# Sheet4.net
KiCad netlist of a schematic drawn in Altium Designer
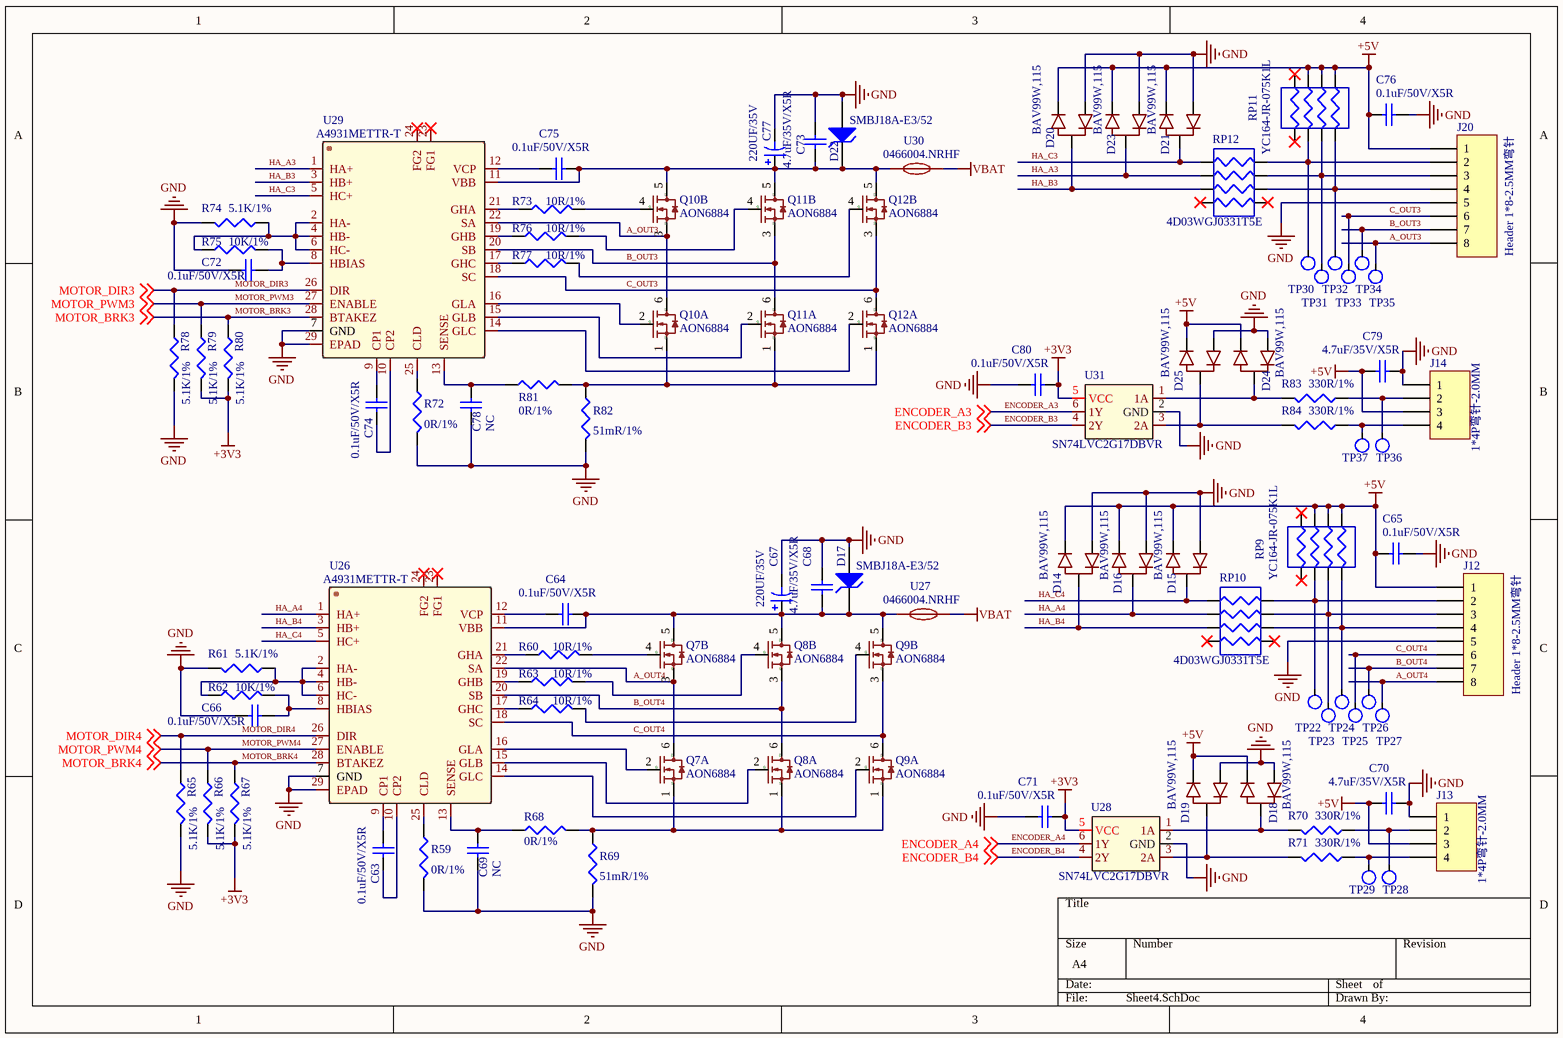
[diagram p0: Sheet4.SchDoc]

(export (version "E")
  (design (tool "Eeschema 10.0.6"))
  (components
    (comp (ref "C63")
      (value "0.1uF/50V/X5R")
      (footprint "C0603")
      (description "Capacitor (Semiconductor SIM Model)")
      (fields (field (name "PUBLISHER") "Altium Limited"))
      (libsource (lib "Miscellaneous Devices") (part "Cap Semi"))
    )
    (comp (ref "C64")
      (value "0.1uF/50V/X5R")
      (footprint "C0603")
      (description "Capacitor (Semiconductor SIM Model)")
      (fields (field (name "PUBLISHER") "Altium Limited"))
      (libsource (lib "Miscellaneous Devices") (part "Cap Semi"))
    )
    (comp (ref "C65")
      (value "0.1uF/50V/X5R")
      (footprint "C0603")
      (description "Capacitor (Semiconductor SIM Model)")
      (fields (field (name "PUBLISHER") "Altium Limited"))
      (libsource (lib "Miscellaneous Devices") (part "Cap Semi"))
    )
    (comp (ref "C66")
      (value "0.1uF/50V/X5R")
      (footprint "C0603")
      (description "Capacitor (Semiconductor SIM Model)")
      (fields (field (name "PUBLISHER") "Altium Limited"))
      (libsource (lib "Miscellaneous Devices") (part "Cap Semi"))
    )
    (comp (ref "C67")
      (value "220UF/35V")
      (footprint "SMD_8X10.2")
      (description "Polarized Capacitor (Radial)")
      (fields (field (name "PUBLISHER") "Altium Limited"))
      (libsource (lib "Miscellaneous Devices") (part "Cap Pol1"))
    )
    (comp (ref "C68")
      (value "4.7uF/35V/X5R")
      (footprint "C0805")
      (description "Capacitor (Semiconductor SIM Model)")
      (fields (field (name "PUBLISHER") "Altium Limited"))
      (libsource (lib "Miscellaneous Devices") (part "Cap Semi"))
    )
    (comp (ref "C69")
      (value "NC")
      (footprint "C0603")
      (description "Capacitor (Semiconductor SIM Model)")
      (fields (field (name "PUBLISHER") "Altium Limited"))
      (libsource (lib "Miscellaneous Devices") (part "Cap Semi"))
    )
    (comp (ref "C70")
      (value "4.7uF/35V/X5R")
      (footprint "C0603")
      (description "Capacitor (Semiconductor SIM Model)")
      (fields (field (name "PUBLISHER") "Altium Limited"))
      (libsource (lib "Miscellaneous Devices") (part "Cap Semi"))
    )
    (comp (ref "C71")
      (value "0.1uF/50V/X5R")
      (footprint "C0603")
      (description "Capacitor (Semiconductor SIM Model)")
      (fields (field (name "PUBLISHER") "Altium Limited"))
      (libsource (lib "Miscellaneous Devices") (part "Cap Semi"))
    )
    (comp (ref "C72")
      (value "0.1uF/50V/X5R")
      (footprint "C0603")
      (description "Capacitor (Semiconductor SIM Model)")
      (fields (field (name "PUBLISHER") "Altium Limited"))
      (libsource (lib "Miscellaneous Devices") (part "Cap Semi"))
    )
    (comp (ref "C73")
      (value "4.7uF/35V/X5R")
      (footprint "C0805")
      (description "Capacitor (Semiconductor SIM Model)")
      (fields (field (name "PUBLISHER") "Altium Limited"))
      (libsource (lib "Miscellaneous Devices") (part "Cap Semi"))
    )
    (comp (ref "C74")
      (value "0.1uF/50V/X5R")
      (footprint "C0603")
      (description "Capacitor (Semiconductor SIM Model)")
      (fields (field (name "PUBLISHER") "Altium Limited"))
      (libsource (lib "Miscellaneous Devices") (part "Cap Semi"))
    )
    (comp (ref "C75")
      (value "0.1uF/50V/X5R")
      (footprint "C0603")
      (description "Capacitor (Semiconductor SIM Model)")
      (fields (field (name "PUBLISHER") "Altium Limited"))
      (libsource (lib "Miscellaneous Devices") (part "Cap Semi"))
    )
    (comp (ref "C76")
      (value "0.1uF/50V/X5R")
      (footprint "C0603")
      (description "Capacitor (Semiconductor SIM Model)")
      (fields (field (name "PUBLISHER") "Altium Limited"))
      (libsource (lib "Miscellaneous Devices") (part "Cap Semi"))
    )
    (comp (ref "C77")
      (value "220UF/35V")
      (footprint "SMD_8X10.2")
      (description "Polarized Capacitor (Radial)")
      (fields (field (name "PUBLISHER") "Altium Limited"))
      (libsource (lib "Miscellaneous Devices") (part "Cap Pol1"))
    )
    (comp (ref "C78")
      (value "NC")
      (footprint "C0603")
      (description "Capacitor (Semiconductor SIM Model)")
      (fields (field (name "PUBLISHER") "Altium Limited"))
      (libsource (lib "Miscellaneous Devices") (part "Cap Semi"))
    )
    (comp (ref "C79")
      (value "4.7uF/35V/X5R")
      (footprint "C0603")
      (description "Capacitor (Semiconductor SIM Model)")
      (fields (field (name "PUBLISHER") "Altium Limited"))
      (libsource (lib "Miscellaneous Devices") (part "Cap Semi"))
    )
    (comp (ref "C80")
      (value "0.1uF/50V/X5R")
      (footprint "C0603")
      (description "Capacitor (Semiconductor SIM Model)")
      (fields (field (name "PUBLISHER") "Altium Limited"))
      (libsource (lib "Miscellaneous Devices") (part "Cap Semi"))
    )
    (comp (ref "D14") (value "BAV99W,115") (libsource (lib "Schlib1") (part "BAV99W,115")))
    (comp (ref "D15") (value "BAV99W,115") (libsource (lib "Schlib1") (part "BAV99W,115")))
    (comp (ref "D16") (value "BAV99W,115") (libsource (lib "Schlib1") (part "BAV99W,115")))
    (comp (ref "D17")
      (value "SMBJ18A-E3/52")
      (footprint "SMB")
      (description "Zener Diode")
      (fields (field (name "PUBLISHER") "Altium Limited"))
      (libsource (lib "Miscellaneous Devices") (part "D Zener"))
    )
    (comp (ref "D18") (value "BAV99W,115") (libsource (lib "Schlib1") (part "BAV99W,115")))
    (comp (ref "D19") (value "BAV99W,115") (libsource (lib "Schlib1") (part "BAV99W,115")))
    (comp (ref "D20") (value "BAV99W,115") (libsource (lib "Schlib1") (part "BAV99W,115")))
    (comp (ref "D21") (value "BAV99W,115") (libsource (lib "Schlib1") (part "BAV99W,115")))
    (comp (ref "D22")
      (value "SMBJ18A-E3/52")
      (footprint "SMB")
      (description "Zener Diode")
      (fields (field (name "PUBLISHER") "Altium Limited"))
      (libsource (lib "Miscellaneous Devices") (part "D Zener"))
    )
    (comp (ref "D23") (value "BAV99W,115") (libsource (lib "Schlib1") (part "BAV99W,115")))
    (comp (ref "D24") (value "BAV99W,115") (libsource (lib "Schlib1") (part "BAV99W,115")))
    (comp (ref "D25") (value "BAV99W,115") (libsource (lib "Schlib1") (part "BAV99W,115")))
    (comp (ref "J12")
      (value "Header 1*8-2.5MM弯针")
      (footprint "DIP_8X2.5")
      (description "Header, 8-Pin")
      (fields (field (name "PUBLISHER") "Altium Limited"))
      (libsource (lib "Miscellaneous Connectors") (part "Header 8"))
    )
    (comp (ref "J13")
      (value "1*4P弯针-2.0MM")
      (footprint "DIP_4X2MM")
      (description "Header, 4-Pin")
      (fields (field (name "PUBLISHER") "Altium Limited"))
      (libsource (lib "Miscellaneous Connectors") (part "Header 4"))
    )
    (comp (ref "J14")
      (value "1*4P弯针-2.0MM")
      (footprint "DIP_4X2MM")
      (description "Header, 4-Pin")
      (fields (field (name "PUBLISHER") "Altium Limited"))
      (libsource (lib "Miscellaneous Connectors") (part "Header 4"))
    )
    (comp (ref "J20")
      (value "Header 1*8-2.5MM弯针")
      (footprint "DIP_8X2.5")
      (description "Header, 8-Pin")
      (fields (field (name "PUBLISHER") "Altium Limited"))
      (libsource (lib "Miscellaneous Connectors") (part "Header 8"))
    )
    (comp (ref "Q7") (value "AON6884") (footprint "AOS") (libsource (lib "Schlib1") (part "AON6884")))
    (comp (ref "Q8") (value "AON6884") (footprint "AOS") (libsource (lib "Schlib1") (part "AON6884")))
    (comp (ref "Q9") (value "AON6884") (footprint "AOS") (libsource (lib "Schlib1") (part "AON6884")))
    (comp (ref "Q10") (value "AON6884") (footprint "AOS") (libsource (lib "Schlib1") (part "AON6884")))
    (comp (ref "Q11") (value "AON6884") (footprint "AOS") (libsource (lib "Schlib1") (part "AON6884")))
    (comp (ref "Q12") (value "AON6884") (footprint "AOS") (libsource (lib "Schlib1") (part "AON6884")))
    (comp (ref "R59")
      (value "0R/1%")
      (footprint "R0603")
      (description "Resistor")
      (fields (field (name "PUBLISHER") "Altium Limited"))
      (libsource (lib "Miscellaneous Devices") (part "Res3"))
    )
    (comp (ref "R60")
      (value "10R/1%")
      (footprint "R0603")
      (description "Resistor")
      (fields (field (name "PUBLISHER") "Altium Limited"))
      (libsource (lib "Miscellaneous Devices") (part "Res3"))
    )
    (comp (ref "R61")
      (value "5.1K/1%")
      (footprint "R0603")
      (description "Resistor")
      (fields (field (name "PUBLISHER") "Altium Limited"))
      (libsource (lib "Miscellaneous Devices") (part "Res3"))
    )
    (comp (ref "R62")
      (value "10K/1%")
      (footprint "R0603")
      (description "Resistor")
      (fields (field (name "PUBLISHER") "Altium Limited"))
      (libsource (lib "Miscellaneous Devices") (part "Res3"))
    )
    (comp (ref "R63")
      (value "10R/1%")
      (footprint "R0603")
      (description "Resistor")
      (fields (field (name "PUBLISHER") "Altium Limited"))
      (libsource (lib "Miscellaneous Devices") (part "Res3"))
    )
    (comp (ref "R64")
      (value "10R/1%")
      (footprint "R0603")
      (description "Resistor")
      (fields (field (name "PUBLISHER") "Altium Limited"))
      (libsource (lib "Miscellaneous Devices") (part "Res3"))
    )
    (comp (ref "R65")
      (value "5.1K/1%")
      (footprint "R0603")
      (description "Resistor")
      (fields (field (name "PUBLISHER") "Altium Limited"))
      (libsource (lib "Miscellaneous Devices") (part "Res3"))
    )
    (comp (ref "R66")
      (value "5.1K/1%")
      (footprint "R0603")
      (description "Resistor")
      (fields (field (name "PUBLISHER") "Altium Limited"))
      (libsource (lib "Miscellaneous Devices") (part "Res3"))
    )
    (comp (ref "R67")
      (value "5.1K/1%")
      (footprint "R0603")
      (description "Resistor")
      (fields (field (name "PUBLISHER") "Altium Limited"))
      (libsource (lib "Miscellaneous Devices") (part "Res3"))
    )
    (comp (ref "R68")
      (value "0R/1%")
      (footprint "R0603")
      (description "Resistor")
      (fields (field (name "PUBLISHER") "Altium Limited"))
      (libsource (lib "Miscellaneous Devices") (part "Res3"))
    )
    (comp (ref "R69")
      (value "51mR/1%")
      (footprint "R0805")
      (description "Resistor")
      (fields (field (name "PUBLISHER") "Altium Limited"))
      (libsource (lib "Miscellaneous Devices") (part "Res3"))
    )
    (comp (ref "R70")
      (value "330R/1%")
      (footprint "R0603")
      (description "Resistor")
      (fields (field (name "PUBLISHER") "Altium Limited"))
      (libsource (lib "Miscellaneous Devices") (part "Res3"))
    )
    (comp (ref "R71")
      (value "330R/1%")
      (footprint "R0603")
      (description "Resistor")
      (fields (field (name "PUBLISHER") "Altium Limited"))
      (libsource (lib "Miscellaneous Devices") (part "Res3"))
    )
    (comp (ref "R72")
      (value "0R/1%")
      (footprint "R0603")
      (description "Resistor")
      (fields (field (name "PUBLISHER") "Altium Limited"))
      (libsource (lib "Miscellaneous Devices") (part "Res3"))
    )
    (comp (ref "R73")
      (value "10R/1%")
      (footprint "R0603")
      (description "Resistor")
      (fields (field (name "PUBLISHER") "Altium Limited"))
      (libsource (lib "Miscellaneous Devices") (part "Res3"))
    )
    (comp (ref "R74")
      (value "5.1K/1%")
      (footprint "R0603")
      (description "Resistor")
      (fields (field (name "PUBLISHER") "Altium Limited"))
      (libsource (lib "Miscellaneous Devices") (part "Res3"))
    )
    (comp (ref "R75")
      (value "10K/1%")
      (footprint "R0603")
      (description "Resistor")
      (fields (field (name "PUBLISHER") "Altium Limited"))
      (libsource (lib "Miscellaneous Devices") (part "Res3"))
    )
    (comp (ref "R76")
      (value "10R/1%")
      (footprint "R0603")
      (description "Resistor")
      (fields (field (name "PUBLISHER") "Altium Limited"))
      (libsource (lib "Miscellaneous Devices") (part "Res3"))
    )
    (comp (ref "R77")
      (value "10R/1%")
      (footprint "R0603")
      (description "Resistor")
      (fields (field (name "PUBLISHER") "Altium Limited"))
      (libsource (lib "Miscellaneous Devices") (part "Res3"))
    )
    (comp (ref "R78")
      (value "5.1K/1%")
      (footprint "R0603")
      (description "Resistor")
      (fields (field (name "PUBLISHER") "Altium Limited"))
      (libsource (lib "Miscellaneous Devices") (part "Res3"))
    )
    (comp (ref "R79")
      (value "5.1K/1%")
      (footprint "R0603")
      (description "Resistor")
      (fields (field (name "PUBLISHER") "Altium Limited"))
      (libsource (lib "Miscellaneous Devices") (part "Res3"))
    )
    (comp (ref "R80")
      (value "5.1K/1%")
      (footprint "R0603")
      (description "Resistor")
      (fields (field (name "PUBLISHER") "Altium Limited"))
      (libsource (lib "Miscellaneous Devices") (part "Res3"))
    )
    (comp (ref "R81")
      (value "0R/1%")
      (footprint "R0603")
      (description "Resistor")
      (fields (field (name "PUBLISHER") "Altium Limited"))
      (libsource (lib "Miscellaneous Devices") (part "Res3"))
    )
    (comp (ref "R82")
      (value "51mR/1%")
      (footprint "R0805")
      (description "Resistor")
      (fields (field (name "PUBLISHER") "Altium Limited"))
      (libsource (lib "Miscellaneous Devices") (part "Res3"))
    )
    (comp (ref "R83")
      (value "330R/1%")
      (footprint "R0603")
      (description "Resistor")
      (fields (field (name "PUBLISHER") "Altium Limited"))
      (libsource (lib "Miscellaneous Devices") (part "Res3"))
    )
    (comp (ref "R84")
      (value "330R/1%")
      (footprint "R0603")
      (description "Resistor")
      (fields (field (name "PUBLISHER") "Altium Limited"))
      (libsource (lib "Miscellaneous Devices") (part "Res3"))
    )
    (comp (ref "RP9") (value "YC164-JR-075K1L") (footprint "RP-1206") (libsource (lib "Schlib1") (part "RP")))
    (comp (ref "RP10") (value "4D03WGJ0331T5E") (footprint "RP-1206") (libsource (lib "Schlib1") (part "RP")))
    (comp (ref "RP11")
      (value "YC164-JR-075K1L")
      (footprint "RP-1206")
      (libsource (lib "Schlib1") (part "RP"))
    )
    (comp (ref "RP12") (value "4D03WGJ0331T5E") (footprint "RP-1206") (libsource (lib "Schlib1") (part "RP")))
    (comp (ref "TP22") (value "TP") (footprint "TP") (libsource (lib "Schlib1") (part "TP")))
    (comp (ref "TP23") (value "TP") (footprint "TP") (libsource (lib "Schlib1") (part "TP")))
    (comp (ref "TP24") (value "TP") (footprint "TP") (libsource (lib "Schlib1") (part "TP")))
    (comp (ref "TP25") (value "TP") (footprint "TP") (libsource (lib "Schlib1") (part "TP")))
    (comp (ref "TP26") (value "TP") (footprint "TP") (libsource (lib "Schlib1") (part "TP")))
    (comp (ref "TP27") (value "TP") (footprint "TP") (libsource (lib "Schlib1") (part "TP")))
    (comp (ref "TP28") (value "TP") (footprint "TP") (libsource (lib "Schlib1") (part "TP")))
    (comp (ref "TP29") (value "TP") (footprint "TP") (libsource (lib "Schlib1") (part "TP")))
    (comp (ref "TP30") (value "TP") (footprint "TP") (libsource (lib "Schlib1") (part "TP")))
    (comp (ref "TP31") (value "TP") (footprint "TP") (libsource (lib "Schlib1") (part "TP")))
    (comp (ref "TP32") (value "TP") (footprint "TP") (libsource (lib "Schlib1") (part "TP")))
    (comp (ref "TP33") (value "TP") (footprint "TP") (libsource (lib "Schlib1") (part "TP")))
    (comp (ref "TP34") (value "TP") (footprint "TP") (libsource (lib "Schlib1") (part "TP")))
    (comp (ref "TP35") (value "TP") (footprint "TP") (libsource (lib "Schlib1") (part "TP")))
    (comp (ref "TP36") (value "TP") (footprint "TP") (libsource (lib "Schlib1") (part "TP")))
    (comp (ref "TP37") (value "TP") (footprint "TP") (libsource (lib "Schlib1") (part "TP")))
    (comp (ref "U26")
      (value "A4931METTR-T")
      (footprint "QFN-28")
      (libsource (lib "Schlib1") (part "A4931METTR-T"))
    )
    (comp (ref "U27")
      (value "0466004.NRHF")
      (footprint "1206")
      (libsource (lib "Schlib1") (part "0466004.NRHF"))
    )
    (comp (ref "U28")
      (value "SN74LVC2G17DBVR")
      (footprint "SOT-23-6")
      (libsource (lib "Schlib1") (part "SN74LVC2G17DBVR"))
    )
    (comp (ref "U29")
      (value "A4931METTR-T")
      (footprint "QFN-28")
      (libsource (lib "Schlib1") (part "A4931METTR-T"))
    )
    (comp (ref "U30")
      (value "0466004.NRHF")
      (footprint "1206")
      (libsource (lib "Schlib1") (part "0466004.NRHF"))
    )
    (comp (ref "U31")
      (value "SN74LVC2G17DBVR")
      (footprint "SOT-23-6")
      (libsource (lib "Schlib1") (part "SN74LVC2G17DBVR"))
    )
  )
  (nets
    (net (code "1") (name "+3V3") (class "Default")
      (node (ref "C71") (pin "1") (pinfunction "1_1") (pintype "passive"))
      (node (ref "C80") (pin "1") (pinfunction "1_1") (pintype "passive"))
      (node (ref "R66") (pin "2") (pinfunction "2_2") (pintype "passive"))
      (node (ref "R67") (pin "2") (pinfunction "2_2") (pintype "passive"))
      (node (ref "R79") (pin "2") (pinfunction "2_2") (pintype "passive"))
      (node (ref "R80") (pin "2") (pinfunction "2_2") (pintype "passive"))
      (node (ref "U28") (pin "5") (pinfunction "VCC_5") (pintype "passive"))
      (node (ref "U31") (pin "5") (pinfunction "VCC_5") (pintype "passive"))
    )
    (net (code "2") (name "+5V") (class "Default")
      (node (ref "C65") (pin "1") (pinfunction "1_1") (pintype "passive"))
      (node (ref "C70") (pin "1") (pinfunction "1_1") (pintype "passive"))
      (node (ref "C76") (pin "1") (pinfunction "1_1") (pintype "passive"))
      (node (ref "C79") (pin "1") (pinfunction "1_1") (pintype "passive"))
      (node (ref "D14") (pin "2") (pinfunction "2_2") (pintype "passive"))
      (node (ref "D15") (pin "2") (pinfunction "2_2") (pintype "passive"))
      (node (ref "D16") (pin "2") (pinfunction "2_2") (pintype "passive"))
      (node (ref "D18") (pin "2") (pinfunction "2_2") (pintype "passive"))
      (node (ref "D19") (pin "2") (pinfunction "2_2") (pintype "passive"))
      (node (ref "D20") (pin "2") (pinfunction "2_2") (pintype "passive"))
      (node (ref "D21") (pin "2") (pinfunction "2_2") (pintype "passive"))
      (node (ref "D23") (pin "2") (pinfunction "2_2") (pintype "passive"))
      (node (ref "D24") (pin "2") (pinfunction "2_2") (pintype "passive"))
      (node (ref "D25") (pin "2") (pinfunction "2_2") (pintype "passive"))
      (node (ref "J12") (pin "1") (pinfunction "1_1") (pintype "passive"))
      (node (ref "J13") (pin "3") (pinfunction "3_3") (pintype "passive"))
      (node (ref "J14") (pin "3") (pinfunction "3_3") (pintype "passive"))
      (node (ref "J20") (pin "1") (pinfunction "1_1") (pintype "passive"))
      (node (ref "RP11") (pin "1") (pinfunction "1_1") (pintype "passive"))
      (node (ref "RP11") (pin "2") (pinfunction "2_2") (pintype "passive"))
      (node (ref "RP11") (pin "3") (pinfunction "3_3") (pintype "passive"))
      (node (ref "RP9") (pin "1") (pinfunction "1_1") (pintype "passive"))
      (node (ref "RP9") (pin "2") (pinfunction "2_2") (pintype "passive"))
      (node (ref "RP9") (pin "3") (pinfunction "3_3") (pintype "passive"))
    )
    (net (code "3") (name "/A_OUT3") (class "Default")
      (node (ref "J20") (pin "8") (pinfunction "8_8") (pintype "passive"))
      (node (ref "Q10") (pin "3") (pinfunction "S_3") (pintype "passive"))
      (node (ref "Q10") (pin "6") (pinfunction "6_6") (pintype "passive"))
      (node (ref "TP35") (pin "1") (pinfunction "1_1") (pintype "passive"))
      (node (ref "U29") (pin "22") (pinfunction "SA_22") (pintype "passive"))
    )
    (net (code "4") (name "/A_OUT4") (class "Default")
      (node (ref "J12") (pin "8") (pinfunction "8_8") (pintype "passive"))
      (node (ref "Q7") (pin "3") (pinfunction "S_3") (pintype "passive"))
      (node (ref "Q7") (pin "6") (pinfunction "6_6") (pintype "passive"))
      (node (ref "TP27") (pin "1") (pinfunction "1_1") (pintype "passive"))
      (node (ref "U26") (pin "22") (pinfunction "SA_22") (pintype "passive"))
    )
    (net (code "5") (name "/B_OUT3") (class "Default")
      (node (ref "J20") (pin "7") (pinfunction "7_7") (pintype "passive"))
      (node (ref "Q11") (pin "3") (pinfunction "S_3") (pintype "passive"))
      (node (ref "Q11") (pin "6") (pinfunction "6_6") (pintype "passive"))
      (node (ref "TP34") (pin "1") (pinfunction "1_1") (pintype "passive"))
      (node (ref "U29") (pin "20") (pinfunction "SB_20") (pintype "passive"))
    )
    (net (code "6") (name "/B_OUT4") (class "Default")
      (node (ref "J12") (pin "7") (pinfunction "7_7") (pintype "passive"))
      (node (ref "Q8") (pin "3") (pinfunction "S_3") (pintype "passive"))
      (node (ref "Q8") (pin "6") (pinfunction "6_6") (pintype "passive"))
      (node (ref "TP26") (pin "1") (pinfunction "1_1") (pintype "passive"))
      (node (ref "U26") (pin "20") (pinfunction "SB_20") (pintype "passive"))
    )
    (net (code "7") (name "/C_OUT3") (class "Default")
      (node (ref "J20") (pin "6") (pinfunction "6_6") (pintype "passive"))
      (node (ref "Q12") (pin "3") (pinfunction "S_3") (pintype "passive"))
      (node (ref "Q12") (pin "6") (pinfunction "6_6") (pintype "passive"))
      (node (ref "TP33") (pin "1") (pinfunction "1_1") (pintype "passive"))
      (node (ref "U29") (pin "18") (pinfunction "SC_18") (pintype "passive"))
    )
    (net (code "8") (name "/C_OUT4") (class "Default")
      (node (ref "J12") (pin "6") (pinfunction "6_6") (pintype "passive"))
      (node (ref "Q9") (pin "3") (pinfunction "S_3") (pintype "passive"))
      (node (ref "Q9") (pin "6") (pinfunction "6_6") (pintype "passive"))
      (node (ref "TP25") (pin "1") (pinfunction "1_1") (pintype "passive"))
      (node (ref "U26") (pin "18") (pinfunction "SC_18") (pintype "passive"))
    )
    (net (code "9") (name "/HA_A3") (class "Default")
      (node (ref "D23") (pin "3") (pinfunction "3_3") (pintype "passive"))
      (node (ref "RP12") (pin "2") (pinfunction "2_2") (pintype "passive"))
      (node (ref "U29") (pin "1") (pinfunction "HA+_1") (pintype "passive"))
    )
    (net (code "10") (name "/HA_A4") (class "Default")
      (node (ref "D16") (pin "3") (pinfunction "3_3") (pintype "passive"))
      (node (ref "RP10") (pin "2") (pinfunction "2_2") (pintype "passive"))
      (node (ref "U26") (pin "1") (pinfunction "HA+_1") (pintype "passive"))
    )
    (net (code "11") (name "/HA_B3") (class "Default")
      (node (ref "D20") (pin "3") (pinfunction "3_3") (pintype "passive"))
      (node (ref "RP12") (pin "3") (pinfunction "3_3") (pintype "passive"))
      (node (ref "U29") (pin "3") (pinfunction "HB+_3") (pintype "passive"))
    )
    (net (code "12") (name "/HA_B4") (class "Default")
      (node (ref "D14") (pin "3") (pinfunction "3_3") (pintype "passive"))
      (node (ref "RP10") (pin "3") (pinfunction "3_3") (pintype "passive"))
      (node (ref "U26") (pin "3") (pinfunction "HB+_3") (pintype "passive"))
    )
    (net (code "13") (name "/HA_C3") (class "Default")
      (node (ref "D21") (pin "3") (pinfunction "3_3") (pintype "passive"))
      (node (ref "RP12") (pin "1") (pinfunction "1_1") (pintype "passive"))
      (node (ref "U29") (pin "5") (pinfunction "HC+_5") (pintype "passive"))
    )
    (net (code "14") (name "/HA_C4") (class "Default")
      (node (ref "D15") (pin "3") (pinfunction "3_3") (pintype "passive"))
      (node (ref "RP10") (pin "1") (pinfunction "1_1") (pintype "passive"))
      (node (ref "U26") (pin "5") (pinfunction "HC+_5") (pintype "passive"))
    )
    (net (code "15") (name "ENCODER_A3") (class "Default")
      (node (ref "U31") (pin "6") (pinfunction "1Y_6") (pintype "passive"))
    )
    (net (code "16") (name "ENCODER_A4") (class "Default")
      (node (ref "U28") (pin "6") (pinfunction "1Y_6") (pintype "passive"))
    )
    (net (code "17") (name "ENCODER_B3") (class "Default")
      (node (ref "U31") (pin "4") (pinfunction "2Y_4") (pintype "passive"))
    )
    (net (code "18") (name "ENCODER_B4") (class "Default")
      (node (ref "U28") (pin "4") (pinfunction "2Y_4") (pintype "passive"))
    )
    (net (code "19") (name "GND") (class "Default")
      (node (ref "C65") (pin "2") (pinfunction "2_2") (pintype "passive"))
      (node (ref "C66") (pin "1") (pinfunction "1_1") (pintype "passive"))
      (node (ref "C67") (pin "2") (pinfunction "2_2") (pintype "passive"))
      (node (ref "C68") (pin "2") (pinfunction "2_2") (pintype "passive"))
      (node (ref "C69") (pin "2") (pinfunction "2_2") (pintype "passive"))
      (node (ref "C70") (pin "2") (pinfunction "2_2") (pintype "passive"))
      (node (ref "C71") (pin "2") (pinfunction "2_2") (pintype "passive"))
      (node (ref "C72") (pin "2") (pinfunction "2_2") (pintype "passive"))
      (node (ref "C73") (pin "2") (pinfunction "2_2") (pintype "passive"))
      (node (ref "C76") (pin "2") (pinfunction "2_2") (pintype "passive"))
      (node (ref "C77") (pin "2") (pinfunction "2_2") (pintype "passive"))
      (node (ref "C78") (pin "2") (pinfunction "2_2") (pintype "passive"))
      (node (ref "C79") (pin "2") (pinfunction "2_2") (pintype "passive"))
      (node (ref "C80") (pin "2") (pinfunction "2_2") (pintype "passive"))
      (node (ref "D14") (pin "1") (pinfunction "1_1") (pintype "passive"))
      (node (ref "D15") (pin "1") (pinfunction "1_1") (pintype "passive"))
      (node (ref "D16") (pin "1") (pinfunction "1_1") (pintype "passive"))
      (node (ref "D17") (pin "1") (pinfunction "A_1") (pintype "passive"))
      (node (ref "D18") (pin "1") (pinfunction "1_1") (pintype "passive"))
      (node (ref "D19") (pin "1") (pinfunction "1_1") (pintype "passive"))
      (node (ref "D20") (pin "1") (pinfunction "1_1") (pintype "passive"))
      (node (ref "D21") (pin "1") (pinfunction "1_1") (pintype "passive"))
      (node (ref "D22") (pin "1") (pinfunction "A_1") (pintype "passive"))
      (node (ref "D23") (pin "1") (pinfunction "1_1") (pintype "passive"))
      (node (ref "D24") (pin "1") (pinfunction "1_1") (pintype "passive"))
      (node (ref "D25") (pin "1") (pinfunction "1_1") (pintype "passive"))
      (node (ref "J12") (pin "5") (pinfunction "5_5") (pintype "passive"))
      (node (ref "J13") (pin "1") (pinfunction "1_1") (pintype "passive"))
      (node (ref "J14") (pin "1") (pinfunction "1_1") (pintype "passive"))
      (node (ref "J20") (pin "5") (pinfunction "5_5") (pintype "passive"))
      (node (ref "R59") (pin "2") (pinfunction "2_2") (pintype "passive"))
      (node (ref "R61") (pin "2") (pinfunction "2_2") (pintype "passive"))
      (node (ref "R65") (pin "2") (pinfunction "2_2") (pintype "passive"))
      (node (ref "R69") (pin "2") (pinfunction "2_2") (pintype "passive"))
      (node (ref "R72") (pin "2") (pinfunction "2_2") (pintype "passive"))
      (node (ref "R74") (pin "2") (pinfunction "2_2") (pintype "passive"))
      (node (ref "R78") (pin "2") (pinfunction "2_2") (pintype "passive"))
      (node (ref "R82") (pin "2") (pinfunction "2_2") (pintype "passive"))
      (node (ref "U26") (pin "29") (pinfunction "EPAD_29") (pintype "passive"))
      (node (ref "U26") (pin "7") (pinfunction "GND_7") (pintype "passive"))
      (node (ref "U28") (pin "2") (pinfunction "GND_2") (pintype "passive"))
      (node (ref "U29") (pin "29") (pinfunction "EPAD_29") (pintype "passive"))
      (node (ref "U29") (pin "7") (pinfunction "GND_7") (pintype "passive"))
      (node (ref "U31") (pin "2") (pinfunction "GND_2") (pintype "passive"))
    )
    (net (code "20") (name "MOTOR_BRK3") (class "Default")
      (node (ref "R80") (pin "1") (pinfunction "1_1") (pintype "passive"))
      (node (ref "U29") (pin "28") (pinfunction "BTAKEZ_28") (pintype "passive"))
    )
    (net (code "21") (name "MOTOR_BRK4") (class "Default")
      (node (ref "R67") (pin "1") (pinfunction "1_1") (pintype "passive"))
      (node (ref "U26") (pin "28") (pinfunction "BTAKEZ_28") (pintype "passive"))
    )
    (net (code "22") (name "MOTOR_DIR3") (class "Default")
      (node (ref "R78") (pin "1") (pinfunction "1_1") (pintype "passive"))
      (node (ref "U29") (pin "26") (pinfunction "DIR_26") (pintype "passive"))
    )
    (net (code "23") (name "MOTOR_DIR4") (class "Default")
      (node (ref "R65") (pin "1") (pinfunction "1_1") (pintype "passive"))
      (node (ref "U26") (pin "26") (pinfunction "DIR_26") (pintype "passive"))
    )
    (net (code "24") (name "MOTOR_PWM3") (class "Default")
      (node (ref "R79") (pin "1") (pinfunction "1_1") (pintype "passive"))
      (node (ref "U29") (pin "27") (pinfunction "ENABLE_27") (pintype "passive"))
    )
    (net (code "25") (name "MOTOR_PWM4") (class "Default")
      (node (ref "R66") (pin "1") (pinfunction "1_1") (pintype "passive"))
      (node (ref "U26") (pin "27") (pinfunction "ENABLE_27") (pintype "passive"))
    )
    (net (code "26") (name "Net-(D17-K)") (class "Default")
      (node (ref "C64") (pin "2") (pinfunction "2_2") (pintype "passive"))
      (node (ref "C67") (pin "1") (pinfunction "1_1") (pintype "passive"))
      (node (ref "C68") (pin "1") (pinfunction "1_1") (pintype "passive"))
      (node (ref "D17") (pin "2") (pinfunction "K_2") (pintype "passive"))
      (node (ref "Q7") (pin "5") (pinfunction "D_5") (pintype "passive"))
      (node (ref "Q8") (pin "5") (pinfunction "D_5") (pintype "passive"))
      (node (ref "Q9") (pin "5") (pinfunction "D_5") (pintype "passive"))
      (node (ref "U26") (pin "11") (pinfunction "VBB_11") (pintype "passive"))
      (node (ref "U27") (pin "1") (pinfunction "1_1") (pintype "passive"))
    )
    (net (code "27") (name "Net-(D22-K)") (class "Default")
      (node (ref "C73") (pin "1") (pinfunction "1_1") (pintype "passive"))
      (node (ref "C75") (pin "2") (pinfunction "2_2") (pintype "passive"))
      (node (ref "C77") (pin "1") (pinfunction "1_1") (pintype "passive"))
      (node (ref "D22") (pin "2") (pinfunction "K_2") (pintype "passive"))
      (node (ref "Q10") (pin "5") (pinfunction "D_5") (pintype "passive"))
      (node (ref "Q11") (pin "5") (pinfunction "D_5") (pintype "passive"))
      (node (ref "Q12") (pin "5") (pinfunction "D_5") (pintype "passive"))
      (node (ref "U29") (pin "11") (pinfunction "VBB_11") (pintype "passive"))
      (node (ref "U30") (pin "2") (pinfunction "2_2") (pintype "passive"))
    )
    (net (code "28") (name "Net-(J12-Pad2)") (class "Default")
      (node (ref "J12") (pin "2") (pinfunction "2_2") (pintype "passive"))
      (node (ref "RP10") (pin "8") (pinfunction "8_8") (pintype "passive"))
      (node (ref "RP9") (pin "6") (pinfunction "6_6") (pintype "passive"))
      (node (ref "TP22") (pin "1") (pinfunction "1_1") (pintype "passive"))
    )
    (net (code "29") (name "Net-(J12-Pad3)") (class "Default")
      (node (ref "J12") (pin "3") (pinfunction "3_3") (pintype "passive"))
      (node (ref "RP10") (pin "7") (pinfunction "7_7") (pintype "passive"))
      (node (ref "RP9") (pin "7") (pinfunction "7_7") (pintype "passive"))
      (node (ref "TP23") (pin "1") (pinfunction "1_1") (pintype "passive"))
    )
    (net (code "30") (name "Net-(J12-Pad4)") (class "Default")
      (node (ref "J12") (pin "4") (pinfunction "4_4") (pintype "passive"))
      (node (ref "RP10") (pin "6") (pinfunction "6_6") (pintype "passive"))
      (node (ref "RP9") (pin "8") (pinfunction "8_8") (pintype "passive"))
      (node (ref "TP24") (pin "1") (pinfunction "1_1") (pintype "passive"))
    )
    (net (code "31") (name "Net-(J13-Pad2)") (class "Default")
      (node (ref "J13") (pin "2") (pinfunction "2_2") (pintype "passive"))
      (node (ref "R70") (pin "1") (pinfunction "1_1") (pintype "passive"))
      (node (ref "TP28") (pin "1") (pinfunction "1_1") (pintype "passive"))
    )
    (net (code "32") (name "Net-(J13-Pad4)") (class "Default")
      (node (ref "J13") (pin "4") (pinfunction "4_4") (pintype "passive"))
      (node (ref "R71") (pin "1") (pinfunction "1_1") (pintype "passive"))
      (node (ref "TP29") (pin "1") (pinfunction "1_1") (pintype "passive"))
    )
    (net (code "33") (name "Net-(J14-Pad2)") (class "Default")
      (node (ref "J14") (pin "2") (pinfunction "2_2") (pintype "passive"))
      (node (ref "R83") (pin "1") (pinfunction "1_1") (pintype "passive"))
      (node (ref "TP36") (pin "1") (pinfunction "1_1") (pintype "passive"))
    )
    (net (code "34") (name "Net-(J14-Pad4)") (class "Default")
      (node (ref "J14") (pin "4") (pinfunction "4_4") (pintype "passive"))
      (node (ref "R84") (pin "1") (pinfunction "1_1") (pintype "passive"))
      (node (ref "TP37") (pin "1") (pinfunction "1_1") (pintype "passive"))
    )
    (net (code "35") (name "Net-(J20-Pad2)") (class "Default")
      (node (ref "J20") (pin "2") (pinfunction "2_2") (pintype "passive"))
      (node (ref "RP11") (pin "6") (pinfunction "6_6") (pintype "passive"))
      (node (ref "RP12") (pin "8") (pinfunction "8_8") (pintype "passive"))
      (node (ref "TP30") (pin "1") (pinfunction "1_1") (pintype "passive"))
    )
    (net (code "36") (name "Net-(J20-Pad3)") (class "Default")
      (node (ref "J20") (pin "3") (pinfunction "3_3") (pintype "passive"))
      (node (ref "RP11") (pin "7") (pinfunction "7_7") (pintype "passive"))
      (node (ref "RP12") (pin "7") (pinfunction "7_7") (pintype "passive"))
      (node (ref "TP31") (pin "1") (pinfunction "1_1") (pintype "passive"))
    )
    (net (code "37") (name "Net-(J20-Pad4)") (class "Default")
      (node (ref "J20") (pin "4") (pinfunction "4_4") (pintype "passive"))
      (node (ref "RP11") (pin "8") (pinfunction "8_8") (pintype "passive"))
      (node (ref "RP12") (pin "6") (pinfunction "6_6") (pintype "passive"))
      (node (ref "TP32") (pin "1") (pinfunction "1_1") (pintype "passive"))
    )
    (net (code "38") (name "Net-(Q7A-G)") (class "Default")
      (node (ref "Q7") (pin "2") (pinfunction "G_2") (pintype "passive"))
      (node (ref "U26") (pin "16") (pinfunction "GLA_16") (pintype "passive"))
    )
    (net (code "39") (name "Net-(Q7A-S)") (class "Default")
      (node (ref "Q7") (pin "1") (pinfunction "S_1") (pintype "passive"))
      (node (ref "Q8") (pin "1") (pinfunction "S_1") (pintype "passive"))
      (node (ref "Q9") (pin "1") (pinfunction "S_1") (pintype "passive"))
      (node (ref "R68") (pin "2") (pinfunction "2_2") (pintype "passive"))
      (node (ref "R69") (pin "1") (pinfunction "1_1") (pintype "passive"))
    )
    (net (code "40") (name "Net-(Q7B-G)") (class "Default")
      (node (ref "Q7") (pin "4") (pinfunction "G_4") (pintype "passive"))
      (node (ref "R60") (pin "2") (pinfunction "2_2") (pintype "passive"))
    )
    (net (code "41") (name "Net-(Q8A-G)") (class "Default")
      (node (ref "Q8") (pin "2") (pinfunction "G_2") (pintype "passive"))
      (node (ref "U26") (pin "15") (pinfunction "GLB_15") (pintype "passive"))
    )
    (net (code "42") (name "Net-(Q8B-G)") (class "Default")
      (node (ref "Q8") (pin "4") (pinfunction "G_4") (pintype "passive"))
      (node (ref "R63") (pin "2") (pinfunction "2_2") (pintype "passive"))
    )
    (net (code "43") (name "Net-(Q9A-G)") (class "Default")
      (node (ref "Q9") (pin "2") (pinfunction "G_2") (pintype "passive"))
      (node (ref "U26") (pin "14") (pinfunction "GLC_14") (pintype "passive"))
    )
    (net (code "44") (name "Net-(Q9B-G)") (class "Default")
      (node (ref "Q9") (pin "4") (pinfunction "G_4") (pintype "passive"))
      (node (ref "R64") (pin "2") (pinfunction "2_2") (pintype "passive"))
    )
    (net (code "45") (name "Net-(Q10A-G)") (class "Default")
      (node (ref "Q10") (pin "2") (pinfunction "G_2") (pintype "passive"))
      (node (ref "U29") (pin "16") (pinfunction "GLA_16") (pintype "passive"))
    )
    (net (code "46") (name "Net-(Q10A-S)") (class "Default")
      (node (ref "Q10") (pin "1") (pinfunction "S_1") (pintype "passive"))
      (node (ref "Q11") (pin "1") (pinfunction "S_1") (pintype "passive"))
      (node (ref "Q12") (pin "1") (pinfunction "S_1") (pintype "passive"))
      (node (ref "R81") (pin "2") (pinfunction "2_2") (pintype "passive"))
      (node (ref "R82") (pin "1") (pinfunction "1_1") (pintype "passive"))
    )
    (net (code "47") (name "Net-(Q10B-G)") (class "Default")
      (node (ref "Q10") (pin "4") (pinfunction "G_4") (pintype "passive"))
      (node (ref "R73") (pin "2") (pinfunction "2_2") (pintype "passive"))
    )
    (net (code "48") (name "Net-(Q11A-G)") (class "Default")
      (node (ref "Q11") (pin "2") (pinfunction "G_2") (pintype "passive"))
      (node (ref "U29") (pin "15") (pinfunction "GLB_15") (pintype "passive"))
    )
    (net (code "49") (name "Net-(Q11B-G)") (class "Default")
      (node (ref "Q11") (pin "4") (pinfunction "G_4") (pintype "passive"))
      (node (ref "R76") (pin "2") (pinfunction "2_2") (pintype "passive"))
    )
    (net (code "50") (name "Net-(Q12A-G)") (class "Default")
      (node (ref "Q12") (pin "2") (pinfunction "G_2") (pintype "passive"))
      (node (ref "U29") (pin "14") (pinfunction "GLC_14") (pintype "passive"))
    )
    (net (code "51") (name "Net-(Q12B-G)") (class "Default")
      (node (ref "Q12") (pin "4") (pinfunction "G_4") (pintype "passive"))
      (node (ref "R77") (pin "2") (pinfunction "2_2") (pintype "passive"))
    )
    (net (code "52") (name "Net-(U26-CLD)") (class "Default")
      (node (ref "R59") (pin "1") (pinfunction "1_1") (pintype "passive"))
      (node (ref "U26") (pin "25") (pinfunction "CLD_25") (pintype "passive"))
    )
    (net (code "53") (name "Net-(U26-CP1)") (class "Default")
      (node (ref "C63") (pin "1") (pinfunction "1_1") (pintype "passive"))
      (node (ref "U26") (pin "9") (pinfunction "CP1_9") (pintype "passive"))
    )
    (net (code "54") (name "Net-(U26-CP2)") (class "Default")
      (node (ref "C63") (pin "2") (pinfunction "2_2") (pintype "passive"))
      (node (ref "U26") (pin "10") (pinfunction "CP2_10") (pintype "passive"))
    )
    (net (code "55") (name "Net-(U26-GHA)") (class "Default")
      (node (ref "R60") (pin "1") (pinfunction "1_1") (pintype "passive"))
      (node (ref "U26") (pin "21") (pinfunction "GHA_21") (pintype "passive"))
    )
    (net (code "56") (name "Net-(U26-GHB)") (class "Default")
      (node (ref "R63") (pin "1") (pinfunction "1_1") (pintype "passive"))
      (node (ref "U26") (pin "19") (pinfunction "GHB_19") (pintype "passive"))
    )
    (net (code "57") (name "Net-(U26-GHC)") (class "Default")
      (node (ref "R64") (pin "1") (pinfunction "1_1") (pintype "passive"))
      (node (ref "U26") (pin "17") (pinfunction "GHC_17") (pintype "passive"))
    )
    (net (code "58") (name "Net-(U26-HA-)") (class "Default")
      (node (ref "R61") (pin "1") (pinfunction "1_1") (pintype "passive"))
      (node (ref "R62") (pin "1") (pinfunction "1_1") (pintype "passive"))
      (node (ref "U26") (pin "2") (pinfunction "HA-_2") (pintype "passive"))
      (node (ref "U26") (pin "4") (pinfunction "HB-_4") (pintype "passive"))
      (node (ref "U26") (pin "6") (pinfunction "HC-_6") (pintype "passive"))
    )
    (net (code "59") (name "Net-(U26-HBIAS)") (class "Default")
      (node (ref "C66") (pin "2") (pinfunction "2_2") (pintype "passive"))
      (node (ref "R62") (pin "2") (pinfunction "2_2") (pintype "passive"))
      (node (ref "U26") (pin "8") (pinfunction "HBIAS_8") (pintype "passive"))
    )
    (net (code "60") (name "Net-(U26-SENSE)") (class "Default")
      (node (ref "C69") (pin "1") (pinfunction "1_1") (pintype "passive"))
      (node (ref "R68") (pin "1") (pinfunction "1_1") (pintype "passive"))
      (node (ref "U26") (pin "13") (pinfunction "SENSE_13") (pintype "passive"))
    )
    (net (code "61") (name "Net-(U26-VCP)") (class "Default")
      (node (ref "C64") (pin "1") (pinfunction "1_1") (pintype "passive"))
      (node (ref "U26") (pin "12") (pinfunction "VCP_12") (pintype "passive"))
    )
    (net (code "62") (name "Net-(U28-1A)") (class "Default")
      (node (ref "D18") (pin "3") (pinfunction "3_3") (pintype "passive"))
      (node (ref "R70") (pin "2") (pinfunction "2_2") (pintype "passive"))
      (node (ref "U28") (pin "1") (pinfunction "1A_1") (pintype "passive"))
    )
    (net (code "63") (name "Net-(U28-2A)") (class "Default")
      (node (ref "D19") (pin "3") (pinfunction "3_3") (pintype "passive"))
      (node (ref "R71") (pin "2") (pinfunction "2_2") (pintype "passive"))
      (node (ref "U28") (pin "3") (pinfunction "2A_3") (pintype "passive"))
    )
    (net (code "64") (name "Net-(U29-CLD)") (class "Default")
      (node (ref "R72") (pin "1") (pinfunction "1_1") (pintype "passive"))
      (node (ref "U29") (pin "25") (pinfunction "CLD_25") (pintype "passive"))
    )
    (net (code "65") (name "Net-(U29-CP1)") (class "Default")
      (node (ref "C74") (pin "1") (pinfunction "1_1") (pintype "passive"))
      (node (ref "U29") (pin "9") (pinfunction "CP1_9") (pintype "passive"))
    )
    (net (code "66") (name "Net-(U29-CP2)") (class "Default")
      (node (ref "C74") (pin "2") (pinfunction "2_2") (pintype "passive"))
      (node (ref "U29") (pin "10") (pinfunction "CP2_10") (pintype "passive"))
    )
    (net (code "67") (name "Net-(U29-GHA)") (class "Default")
      (node (ref "R73") (pin "1") (pinfunction "1_1") (pintype "passive"))
      (node (ref "U29") (pin "21") (pinfunction "GHA_21") (pintype "passive"))
    )
    (net (code "68") (name "Net-(U29-GHB)") (class "Default")
      (node (ref "R76") (pin "1") (pinfunction "1_1") (pintype "passive"))
      (node (ref "U29") (pin "19") (pinfunction "GHB_19") (pintype "passive"))
    )
    (net (code "69") (name "Net-(U29-GHC)") (class "Default")
      (node (ref "R77") (pin "1") (pinfunction "1_1") (pintype "passive"))
      (node (ref "U29") (pin "17") (pinfunction "GHC_17") (pintype "passive"))
    )
    (net (code "70") (name "Net-(U29-HA-)") (class "Default")
      (node (ref "R74") (pin "1") (pinfunction "1_1") (pintype "passive"))
      (node (ref "R75") (pin "1") (pinfunction "1_1") (pintype "passive"))
      (node (ref "U29") (pin "2") (pinfunction "HA-_2") (pintype "passive"))
      (node (ref "U29") (pin "4") (pinfunction "HB-_4") (pintype "passive"))
      (node (ref "U29") (pin "6") (pinfunction "HC-_6") (pintype "passive"))
    )
    (net (code "71") (name "Net-(U29-HBIAS)") (class "Default")
      (node (ref "C72") (pin "1") (pinfunction "1_1") (pintype "passive"))
      (node (ref "R75") (pin "2") (pinfunction "2_2") (pintype "passive"))
      (node (ref "U29") (pin "8") (pinfunction "HBIAS_8") (pintype "passive"))
    )
    (net (code "72") (name "Net-(U29-SENSE)") (class "Default")
      (node (ref "C78") (pin "1") (pinfunction "1_1") (pintype "passive"))
      (node (ref "R81") (pin "1") (pinfunction "1_1") (pintype "passive"))
      (node (ref "U29") (pin "13") (pinfunction "SENSE_13") (pintype "passive"))
    )
    (net (code "73") (name "Net-(U29-VCP)") (class "Default")
      (node (ref "C75") (pin "1") (pinfunction "1_1") (pintype "passive"))
      (node (ref "U29") (pin "12") (pinfunction "VCP_12") (pintype "passive"))
    )
    (net (code "74") (name "Net-(U31-1A)") (class "Default")
      (node (ref "D24") (pin "3") (pinfunction "3_3") (pintype "passive"))
      (node (ref "R83") (pin "2") (pinfunction "2_2") (pintype "passive"))
      (node (ref "U31") (pin "1") (pinfunction "1A_1") (pintype "passive"))
    )
    (net (code "75") (name "Net-(U31-2A)") (class "Default")
      (node (ref "D25") (pin "3") (pinfunction "3_3") (pintype "passive"))
      (node (ref "R84") (pin "2") (pinfunction "2_2") (pintype "passive"))
      (node (ref "U31") (pin "3") (pinfunction "2A_3") (pintype "passive"))
    )
    (net (code "76") (name "VBAT") (class "Default")
      (node (ref "U27") (pin "2") (pinfunction "2_2") (pintype "passive"))
      (node (ref "U30") (pin "1") (pinfunction "1_1") (pintype "passive"))
    )
    (net (code "77") (name "unconnected-(RP9-Pad4)") (class "Default")
      (node (ref "RP9") (pin "4") (pinfunction "4_4") (pintype "passive+no_connect"))
    )
    (net (code "78") (name "unconnected-(RP9-Pad5)") (class "Default")
      (node (ref "RP9") (pin "5") (pinfunction "5_5") (pintype "passive+no_connect"))
    )
    (net (code "79") (name "unconnected-(RP10-Pad4)") (class "Default")
      (node (ref "RP10") (pin "4") (pinfunction "4_4") (pintype "passive+no_connect"))
    )
    (net (code "80") (name "unconnected-(RP10-Pad5)") (class "Default")
      (node (ref "RP10") (pin "5") (pinfunction "5_5") (pintype "passive+no_connect"))
    )
    (net (code "81") (name "unconnected-(RP11-Pad4)") (class "Default")
      (node (ref "RP11") (pin "4") (pinfunction "4_4") (pintype "passive+no_connect"))
    )
    (net (code "82") (name "unconnected-(RP11-Pad5)") (class "Default")
      (node (ref "RP11") (pin "5") (pinfunction "5_5") (pintype "passive+no_connect"))
    )
    (net (code "83") (name "unconnected-(RP12-Pad4)") (class "Default")
      (node (ref "RP12") (pin "4") (pinfunction "4_4") (pintype "passive+no_connect"))
    )
    (net (code "84") (name "unconnected-(RP12-Pad5)") (class "Default")
      (node (ref "RP12") (pin "5") (pinfunction "5_5") (pintype "passive+no_connect"))
    )
    (net (code "85") (name "unconnected-(U26-FG1-Pad23)") (class "Default")
      (node (ref "U26") (pin "23") (pinfunction "FG1_23") (pintype "passive+no_connect"))
    )
    (net (code "86") (name "unconnected-(U26-FG2-Pad24)") (class "Default")
      (node (ref "U26") (pin "24") (pinfunction "FG2_24") (pintype "passive+no_connect"))
    )
    (net (code "87") (name "unconnected-(U29-FG1-Pad23)") (class "Default")
      (node (ref "U29") (pin "23") (pinfunction "FG1_23") (pintype "passive+no_connect"))
    )
    (net (code "88") (name "unconnected-(U29-FG2-Pad24)") (class "Default")
      (node (ref "U29") (pin "24") (pinfunction "FG2_24") (pintype "passive+no_connect"))
    )
  )
)
